# RSD_M1_HELMET_UNIT_POWER_STOP_LIGHT_V2.net
KiCad netlist of a schematic drawn in Altium Designer
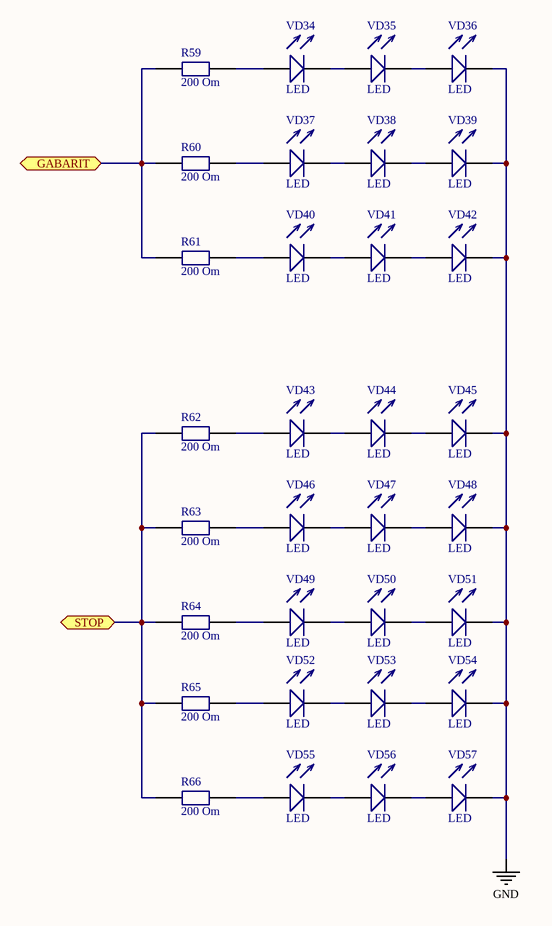
[diagram p0: RSD_M1_HELMET_UNIT_POWER_STOP_LIGHT_V2.SchDoc]

(export (version "E")
  (design (tool "Eeschema 10.0.6"))
  (components
    (comp (ref "R59")
      (value "200 Om")
      (footprint "Res0603")
      (fields (field (name "Comment") "Resistor"))
      (libsource (lib "my_library") (part "Resistor"))
    )
    (comp (ref "R60")
      (value "200 Om")
      (footprint "Res0603")
      (fields (field (name "Comment") "Resistor"))
      (libsource (lib "my_library") (part "Resistor"))
    )
    (comp (ref "R61")
      (value "200 Om")
      (footprint "Res0603")
      (fields (field (name "Comment") "Resistor"))
      (libsource (lib "my_library") (part "Resistor"))
    )
    (comp (ref "R62")
      (value "200 Om")
      (footprint "Res0603")
      (fields (field (name "Comment") "Resistor"))
      (libsource (lib "my_library") (part "Resistor"))
    )
    (comp (ref "R63")
      (value "200 Om")
      (footprint "Res0603")
      (fields (field (name "Comment") "Resistor"))
      (libsource (lib "my_library") (part "Resistor"))
    )
    (comp (ref "R64")
      (value "200 Om")
      (footprint "Res0603")
      (fields (field (name "Comment") "Resistor"))
      (libsource (lib "my_library") (part "Resistor"))
    )
    (comp (ref "R65")
      (value "200 Om")
      (footprint "Res0603")
      (fields (field (name "Comment") "Resistor"))
      (libsource (lib "my_library") (part "Resistor"))
    )
    (comp (ref "R66")
      (value "200 Om")
      (footprint "Res0603")
      (fields (field (name "Comment") "Resistor"))
      (libsource (lib "my_library") (part "Resistor"))
    )
    (comp (ref "VD34") (value "LED") (footprint "3528_LED") (libsource (lib "my_library") (part "LED")))
    (comp (ref "VD35") (value "LED") (footprint "3528_LED") (libsource (lib "my_library") (part "LED")))
    (comp (ref "VD36") (value "LED") (footprint "3528_LED") (libsource (lib "my_library") (part "LED")))
    (comp (ref "VD37") (value "LED") (footprint "3528_LED") (libsource (lib "my_library") (part "LED")))
    (comp (ref "VD38") (value "LED") (footprint "3528_LED") (libsource (lib "my_library") (part "LED")))
    (comp (ref "VD39") (value "LED") (footprint "3528_LED") (libsource (lib "my_library") (part "LED")))
    (comp (ref "VD40") (value "LED") (footprint "3528_LED") (libsource (lib "my_library") (part "LED")))
    (comp (ref "VD41") (value "LED") (footprint "3528_LED") (libsource (lib "my_library") (part "LED")))
    (comp (ref "VD42") (value "LED") (footprint "3528_LED") (libsource (lib "my_library") (part "LED")))
    (comp (ref "VD43") (value "LED") (footprint "3528_LED") (libsource (lib "my_library") (part "LED")))
    (comp (ref "VD44") (value "LED") (footprint "3528_LED") (libsource (lib "my_library") (part "LED")))
    (comp (ref "VD45") (value "LED") (footprint "3528_LED") (libsource (lib "my_library") (part "LED")))
    (comp (ref "VD46") (value "LED") (footprint "3528_LED") (libsource (lib "my_library") (part "LED")))
    (comp (ref "VD47") (value "LED") (footprint "3528_LED") (libsource (lib "my_library") (part "LED")))
    (comp (ref "VD48") (value "LED") (footprint "3528_LED") (libsource (lib "my_library") (part "LED")))
    (comp (ref "VD49") (value "LED") (footprint "3528_LED") (libsource (lib "my_library") (part "LED")))
    (comp (ref "VD50") (value "LED") (footprint "3528_LED") (libsource (lib "my_library") (part "LED")))
    (comp (ref "VD51") (value "LED") (footprint "3528_LED") (libsource (lib "my_library") (part "LED")))
    (comp (ref "VD52") (value "LED") (footprint "3528_LED") (libsource (lib "my_library") (part "LED")))
    (comp (ref "VD53") (value "LED") (footprint "3528_LED") (libsource (lib "my_library") (part "LED")))
    (comp (ref "VD54") (value "LED") (footprint "3528_LED") (libsource (lib "my_library") (part "LED")))
    (comp (ref "VD55") (value "LED") (footprint "3528_LED") (libsource (lib "my_library") (part "LED")))
    (comp (ref "VD56") (value "LED") (footprint "3528_LED") (libsource (lib "my_library") (part "LED")))
    (comp (ref "VD57") (value "LED") (footprint "3528_LED") (libsource (lib "my_library") (part "LED")))
  )
  (nets
    (net (code "1") (name "/GABARIT") (class "Default")
      (node (ref "R59") (pin "2") (pinfunction "2_2") (pintype "passive"))
      (node (ref "R60") (pin "2") (pinfunction "2_2") (pintype "passive"))
      (node (ref "R61") (pin "2") (pinfunction "2_2") (pintype "passive"))
    )
    (net (code "2") (name "/STOP") (class "Default")
      (node (ref "R62") (pin "2") (pinfunction "2_2") (pintype "passive"))
      (node (ref "R63") (pin "2") (pinfunction "2_2") (pintype "passive"))
      (node (ref "R64") (pin "2") (pinfunction "2_2") (pintype "passive"))
      (node (ref "R65") (pin "2") (pinfunction "2_2") (pintype "passive"))
      (node (ref "R66") (pin "2") (pinfunction "2_2") (pintype "passive"))
    )
    (net (code "3") (name "GND") (class "Default")
      (node (ref "VD36") (pin "1") (pinfunction "1_1") (pintype "passive"))
      (node (ref "VD39") (pin "1") (pinfunction "1_1") (pintype "passive"))
      (node (ref "VD42") (pin "1") (pinfunction "1_1") (pintype "passive"))
      (node (ref "VD45") (pin "1") (pinfunction "1_1") (pintype "passive"))
      (node (ref "VD48") (pin "1") (pinfunction "1_1") (pintype "passive"))
      (node (ref "VD51") (pin "1") (pinfunction "1_1") (pintype "passive"))
      (node (ref "VD54") (pin "1") (pinfunction "1_1") (pintype "passive"))
      (node (ref "VD57") (pin "1") (pinfunction "1_1") (pintype "passive"))
    )
    (net (code "4") (name "Net-(R59-Pad1)") (class "Default")
      (node (ref "R59") (pin "1") (pinfunction "1_1") (pintype "passive"))
      (node (ref "VD34") (pin "2") (pinfunction "2_2") (pintype "passive"))
    )
    (net (code "5") (name "Net-(R60-Pad1)") (class "Default")
      (node (ref "R60") (pin "1") (pinfunction "1_1") (pintype "passive"))
      (node (ref "VD37") (pin "2") (pinfunction "2_2") (pintype "passive"))
    )
    (net (code "6") (name "Net-(R61-Pad1)") (class "Default")
      (node (ref "R61") (pin "1") (pinfunction "1_1") (pintype "passive"))
      (node (ref "VD40") (pin "2") (pinfunction "2_2") (pintype "passive"))
    )
    (net (code "7") (name "Net-(R62-Pad1)") (class "Default")
      (node (ref "R62") (pin "1") (pinfunction "1_1") (pintype "passive"))
      (node (ref "VD43") (pin "2") (pinfunction "2_2") (pintype "passive"))
    )
    (net (code "8") (name "Net-(R63-Pad1)") (class "Default")
      (node (ref "R63") (pin "1") (pinfunction "1_1") (pintype "passive"))
      (node (ref "VD46") (pin "2") (pinfunction "2_2") (pintype "passive"))
    )
    (net (code "9") (name "Net-(R64-Pad1)") (class "Default")
      (node (ref "R64") (pin "1") (pinfunction "1_1") (pintype "passive"))
      (node (ref "VD49") (pin "2") (pinfunction "2_2") (pintype "passive"))
    )
    (net (code "10") (name "Net-(R65-Pad1)") (class "Default")
      (node (ref "R65") (pin "1") (pinfunction "1_1") (pintype "passive"))
      (node (ref "VD52") (pin "2") (pinfunction "2_2") (pintype "passive"))
    )
    (net (code "11") (name "Net-(R66-Pad1)") (class "Default")
      (node (ref "R66") (pin "1") (pinfunction "1_1") (pintype "passive"))
      (node (ref "VD55") (pin "2") (pinfunction "2_2") (pintype "passive"))
    )
    (net (code "12") (name "Net-(VD34-Pad1)") (class "Default")
      (node (ref "VD34") (pin "1") (pinfunction "1_1") (pintype "passive"))
      (node (ref "VD35") (pin "2") (pinfunction "2_2") (pintype "passive"))
    )
    (net (code "13") (name "Net-(VD35-Pad1)") (class "Default")
      (node (ref "VD35") (pin "1") (pinfunction "1_1") (pintype "passive"))
      (node (ref "VD36") (pin "2") (pinfunction "2_2") (pintype "passive"))
    )
    (net (code "14") (name "Net-(VD37-Pad1)") (class "Default")
      (node (ref "VD37") (pin "1") (pinfunction "1_1") (pintype "passive"))
      (node (ref "VD38") (pin "2") (pinfunction "2_2") (pintype "passive"))
    )
    (net (code "15") (name "Net-(VD38-Pad1)") (class "Default")
      (node (ref "VD38") (pin "1") (pinfunction "1_1") (pintype "passive"))
      (node (ref "VD39") (pin "2") (pinfunction "2_2") (pintype "passive"))
    )
    (net (code "16") (name "Net-(VD40-Pad1)") (class "Default")
      (node (ref "VD40") (pin "1") (pinfunction "1_1") (pintype "passive"))
      (node (ref "VD41") (pin "2") (pinfunction "2_2") (pintype "passive"))
    )
    (net (code "17") (name "Net-(VD41-Pad1)") (class "Default")
      (node (ref "VD41") (pin "1") (pinfunction "1_1") (pintype "passive"))
      (node (ref "VD42") (pin "2") (pinfunction "2_2") (pintype "passive"))
    )
    (net (code "18") (name "Net-(VD43-Pad1)") (class "Default")
      (node (ref "VD43") (pin "1") (pinfunction "1_1") (pintype "passive"))
      (node (ref "VD44") (pin "2") (pinfunction "2_2") (pintype "passive"))
    )
    (net (code "19") (name "Net-(VD44-Pad1)") (class "Default")
      (node (ref "VD44") (pin "1") (pinfunction "1_1") (pintype "passive"))
      (node (ref "VD45") (pin "2") (pinfunction "2_2") (pintype "passive"))
    )
    (net (code "20") (name "Net-(VD46-Pad1)") (class "Default")
      (node (ref "VD46") (pin "1") (pinfunction "1_1") (pintype "passive"))
      (node (ref "VD47") (pin "2") (pinfunction "2_2") (pintype "passive"))
    )
    (net (code "21") (name "Net-(VD47-Pad1)") (class "Default")
      (node (ref "VD47") (pin "1") (pinfunction "1_1") (pintype "passive"))
      (node (ref "VD48") (pin "2") (pinfunction "2_2") (pintype "passive"))
    )
    (net (code "22") (name "Net-(VD49-Pad1)") (class "Default")
      (node (ref "VD49") (pin "1") (pinfunction "1_1") (pintype "passive"))
      (node (ref "VD50") (pin "2") (pinfunction "2_2") (pintype "passive"))
    )
    (net (code "23") (name "Net-(VD50-Pad1)") (class "Default")
      (node (ref "VD50") (pin "1") (pinfunction "1_1") (pintype "passive"))
      (node (ref "VD51") (pin "2") (pinfunction "2_2") (pintype "passive"))
    )
    (net (code "24") (name "Net-(VD52-Pad1)") (class "Default")
      (node (ref "VD52") (pin "1") (pinfunction "1_1") (pintype "passive"))
      (node (ref "VD53") (pin "2") (pinfunction "2_2") (pintype "passive"))
    )
    (net (code "25") (name "Net-(VD53-Pad1)") (class "Default")
      (node (ref "VD53") (pin "1") (pinfunction "1_1") (pintype "passive"))
      (node (ref "VD54") (pin "2") (pinfunction "2_2") (pintype "passive"))
    )
    (net (code "26") (name "Net-(VD55-Pad1)") (class "Default")
      (node (ref "VD55") (pin "1") (pinfunction "1_1") (pintype "passive"))
      (node (ref "VD56") (pin "2") (pinfunction "2_2") (pintype "passive"))
    )
    (net (code "27") (name "Net-(VD56-Pad1)") (class "Default")
      (node (ref "VD56") (pin "1") (pinfunction "1_1") (pintype "passive"))
      (node (ref "VD57") (pin "2") (pinfunction "2_2") (pintype "passive"))
    )
  )
)
